# ESP8266_1wire_Gateway.net
KiCad netlist of a schematic drawn in EAGLE
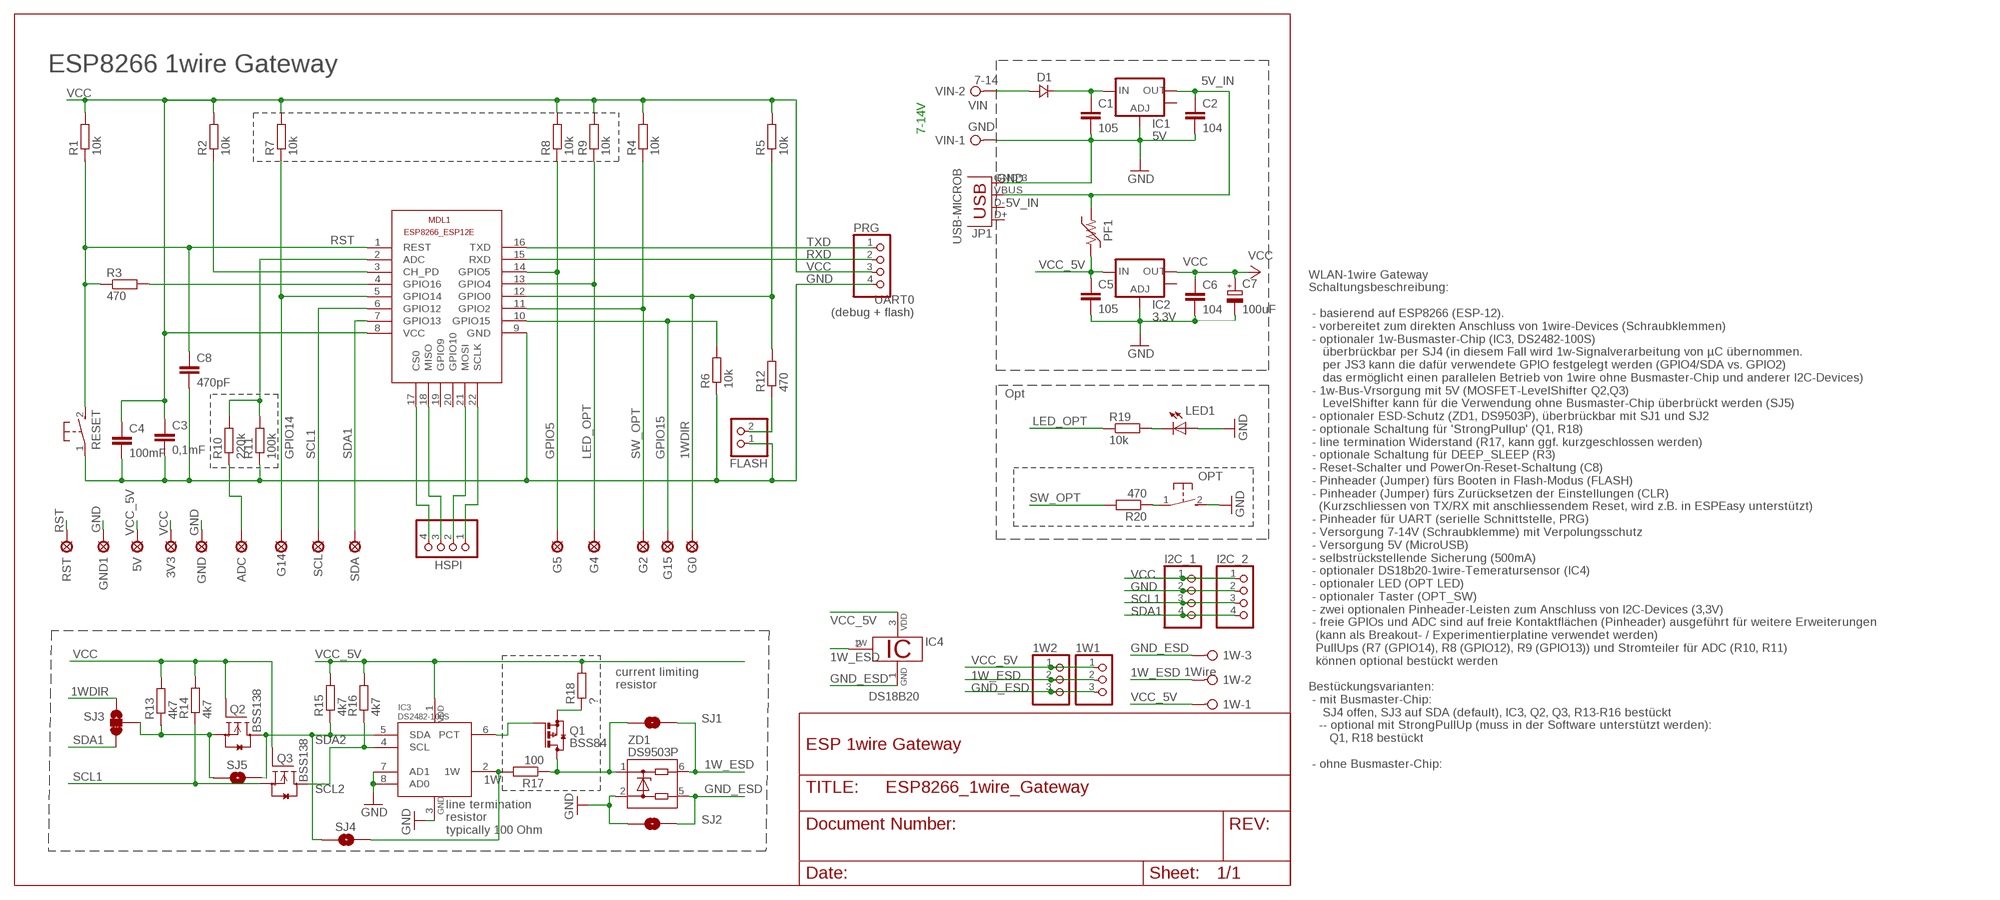
[diagram p0: schematic, sheet 1]

(export (version "E")
  (design (tool "Eeschema 10.0.6"))
  (components
    (comp (ref "1W")
      (value "1Wire")
      (footprint "eagle-import:W237-133")
      (libsource (lib "eagle-import") (part "W237-03P"))
    )
    (comp (ref "1W1")
      (value "PINHD-1X3_S")
      (footprint "eagle-import:1X03")
      (libsource (lib "eagle-import") (part "PINHD-1X3_S"))
    )
    (comp (ref "1W2")
      (value "PINHD-1X3_S")
      (footprint "eagle-import:1X03")
      (libsource (lib "eagle-import") (part "PINHD-1X3_S"))
    )
    (comp (ref "3V3")
      (value "LSP10")
      (footprint "eagle-import:LSP10")
      (libsource (lib "eagle-import") (part "LSP10"))
    )
    (comp (ref "5V")
      (value "LSP10")
      (footprint "eagle-import:LSP10")
      (libsource (lib "eagle-import") (part "LSP10"))
    )
    (comp (ref "ADC")
      (value "LSP10")
      (footprint "eagle-import:LSP10")
      (libsource (lib "eagle-import") (part "LSP10"))
    )
    (comp (ref "C1")
      (value "105")
      (footprint "eagle-import:C0805")
      (libsource (lib "eagle-import") (part "C-EUC0805"))
    )
    (comp (ref "C2")
      (value "104")
      (footprint "eagle-import:C0805")
      (libsource (lib "eagle-import") (part "C-EUC0805"))
    )
    (comp (ref "C3")
      (value "0,1mF")
      (footprint "eagle-import:C0805")
      (libsource (lib "eagle-import") (part "C-EUC0805"))
    )
    (comp (ref "C4")
      (value "100mF")
      (footprint "eagle-import:C1210")
      (libsource (lib "eagle-import") (part "C-EUC1210"))
    )
    (comp (ref "C5")
      (value "105")
      (footprint "eagle-import:C0805")
      (libsource (lib "eagle-import") (part "C-EUC0805"))
    )
    (comp (ref "C6")
      (value "104")
      (footprint "eagle-import:C0805")
      (libsource (lib "eagle-import") (part "C-EUC0805"))
    )
    (comp (ref "C7")
      (value "100uF")
      (footprint "eagle-import:E2,5-6E")
      (libsource (lib "eagle-import") (part "CPOL-EUE2,5-6E"))
    )
    (comp (ref "C8")
      (value "470pF")
      (footprint "eagle-import:C0805")
      (libsource (lib "eagle-import") (part "C-EUC0805"))
    )
    (comp (ref "D1")
      (value "SS14")
      (footprint "eagle-import:DO214")
      (libsource (lib "eagle-import") (part "SS14"))
    )
    (comp (ref "FLASH")
      (value "PINHD-1X2_S")
      (footprint "eagle-import:1X02")
      (libsource (lib "eagle-import") (part "PINHD-1X2_S"))
    )
    (comp (ref "G0")
      (value "LSP10")
      (footprint "eagle-import:LSP10")
      (libsource (lib "eagle-import") (part "LSP10"))
    )
    (comp (ref "G2")
      (value "LSP10")
      (footprint "eagle-import:LSP10")
      (libsource (lib "eagle-import") (part "LSP10"))
    )
    (comp (ref "G4")
      (value "LSP10")
      (footprint "eagle-import:LSP10")
      (libsource (lib "eagle-import") (part "LSP10"))
    )
    (comp (ref "G5")
      (value "LSP10")
      (footprint "eagle-import:LSP10")
      (libsource (lib "eagle-import") (part "LSP10"))
    )
    (comp (ref "G14")
      (value "LSP10")
      (footprint "eagle-import:LSP10")
      (libsource (lib "eagle-import") (part "LSP10"))
    )
    (comp (ref "G15")
      (value "LSP10")
      (footprint "eagle-import:LSP10")
      (libsource (lib "eagle-import") (part "LSP10"))
    )
    (comp (ref "GND")
      (value "LSP10")
      (footprint "eagle-import:LSP10")
      (libsource (lib "eagle-import") (part "LSP10"))
    )
    (comp (ref "GND1")
      (value "GND")
      (footprint "eagle-import:LSP10")
      (libsource (lib "eagle-import") (part "LSP10"))
    )
    (comp (ref "HSPI")
      (value "PINHD-1X4_S")
      (footprint "eagle-import:1X04")
      (libsource (lib "eagle-import") (part "PINHD-1X4_S"))
    )
    (comp (ref "I2C_1")
      (value "PINHD-1X4_S")
      (footprint "eagle-import:1X04")
      (libsource (lib "eagle-import") (part "PINHD-1X4_S"))
    )
    (comp (ref "I2C_2")
      (value "PINHD-1X4_S")
      (footprint "eagle-import:1X04")
      (libsource (lib "eagle-import") (part "PINHD-1X4_S"))
    )
    (comp (ref "IC1")
      (value "5V")
      (footprint "eagle-import:SOT223")
      (libsource (lib "eagle-import") (part "V_REG_LM1117SOT223"))
    )
    (comp (ref "IC2")
      (value "3.3V")
      (footprint "eagle-import:SOT223")
      (libsource (lib "eagle-import") (part "V_REG_LM1117SOT223"))
    )
    (comp (ref "IC3")
      (value "DS2482-100S")
      (footprint "eagle-import:SO08")
      (libsource (lib "eagle-import") (part "DS2482-100S"))
    )
    (comp (ref "IC4")
      (value "DS18B20")
      (footprint "eagle-import:TO92-")
      (libsource (lib "eagle-import") (part "DS18B20"))
    )
    (comp (ref "JP1")
      (value "USB-MICROB")
      (footprint "eagle-import:USB-MICROB")
      (libsource (lib "eagle-import") (part "USB-MICROB"))
    )
    (comp (ref "LED1")
      (value "CFG")
      (footprint "eagle-import:CHIPLED_1206")
      (libsource (lib "eagle-import") (part "LEDCHIPLED_1206"))
    )
    (comp (ref "MDL1")
      (value "µC")
      (footprint "eagle-import:ESP8266-ESP12E")
      (libsource (lib "eagle-import") (part "ESP8266-12EESP8266-ESP12E"))
    )
    (comp (ref "OPT")
      (value "DTSM-3")
      (footprint "eagle-import:DTSM-3")
      (libsource (lib "eagle-import") (part "DTSM-3"))
    )
    (comp (ref "PF1")
      (value "500mA")
      (footprint "eagle-import:F1206")
      (libsource (lib "eagle-import") (part "PTC-F1206"))
    )
    (comp (ref "PRG")
      (value "PINHD-1X4_S")
      (footprint "eagle-import:1X04")
      (libsource (lib "eagle-import") (part "PINHD-1X4_S"))
    )
    (comp (ref "Q1")
      (value "BSS84")
      (footprint "eagle-import:SOT23")
      (libsource (lib "eagle-import") (part "BSS84"))
    )
    (comp (ref "Q2")
      (value "BSS138")
      (footprint "eagle-import:SOT23")
      (libsource (lib "eagle-import") (part "BSS138"))
    )
    (comp (ref "Q3")
      (value "BSS138")
      (footprint "eagle-import:SOT23")
      (libsource (lib "eagle-import") (part "BSS138"))
    )
    (comp (ref "R1")
      (value "10k")
      (footprint "eagle-import:R0805")
      (libsource (lib "eagle-import") (part "resistor_R-EU_R0805"))
    )
    (comp (ref "R2")
      (value "10k")
      (footprint "eagle-import:R0805")
      (libsource (lib "eagle-import") (part "resistor_R-EU_R0805"))
    )
    (comp (ref "R3")
      (value "470")
      (footprint "eagle-import:R0805")
      (libsource (lib "eagle-import") (part "resistor_R-EU_R0805"))
    )
    (comp (ref "R4")
      (value "10k")
      (footprint "eagle-import:R0805")
      (libsource (lib "eagle-import") (part "resistor_R-EU_R0805"))
    )
    (comp (ref "R5")
      (value "10k")
      (footprint "eagle-import:R0805")
      (libsource (lib "eagle-import") (part "resistor_R-EU_R0805"))
    )
    (comp (ref "R6")
      (value "10k")
      (footprint "eagle-import:R0805")
      (libsource (lib "eagle-import") (part "resistor_R-EU_R0805"))
    )
    (comp (ref "R7")
      (value "10k")
      (footprint "eagle-import:R0805")
      (libsource (lib "eagle-import") (part "resistor_R-EU_R0805"))
    )
    (comp (ref "R8")
      (value "10k")
      (footprint "eagle-import:R0805")
      (libsource (lib "eagle-import") (part "resistor_R-EU_R0805"))
    )
    (comp (ref "R9")
      (value "10k")
      (footprint "eagle-import:R0805")
      (libsource (lib "eagle-import") (part "resistor_R-EU_R0805"))
    )
    (comp (ref "R10")
      (value "220k")
      (footprint "eagle-import:R0805")
      (libsource (lib "eagle-import") (part "resistor_R-EU_R0805"))
    )
    (comp (ref "R11")
      (value "100k")
      (footprint "eagle-import:R0805")
      (libsource (lib "eagle-import") (part "resistor_R-EU_R0805"))
    )
    (comp (ref "R12")
      (value "470")
      (footprint "eagle-import:R0805")
      (libsource (lib "eagle-import") (part "resistor_R-EU_R0805"))
    )
    (comp (ref "R13")
      (value "4k7")
      (footprint "eagle-import:R0805")
      (libsource (lib "eagle-import") (part "resistor_R-EU_R0805"))
    )
    (comp (ref "R14")
      (value "4k7")
      (footprint "eagle-import:R0805")
      (libsource (lib "eagle-import") (part "resistor_R-EU_R0805"))
    )
    (comp (ref "R15")
      (value "4k7")
      (footprint "eagle-import:R0805")
      (libsource (lib "eagle-import") (part "resistor_R-EU_R0805"))
    )
    (comp (ref "R16")
      (value "4k7")
      (footprint "eagle-import:R0805")
      (libsource (lib "eagle-import") (part "resistor_R-EU_R0805"))
    )
    (comp (ref "R17")
      (value "100")
      (footprint "eagle-import:R0805_SMALL_GAP")
      (libsource (lib "eagle-import") (part "R0805_SMALL_GAP"))
    )
    (comp (ref "R18")
      (value "?")
      (footprint "eagle-import:R0805_SMALL_GAP")
      (libsource (lib "eagle-import") (part "R0805_SMALL_GAP"))
    )
    (comp (ref "R19")
      (value "10k")
      (footprint "eagle-import:R0805")
      (libsource (lib "eagle-import") (part "R-EU_R0805"))
    )
    (comp (ref "R20")
      (value "470")
      (footprint "eagle-import:R0805")
      (libsource (lib "eagle-import") (part "resistor_R-EU_R0805"))
    )
    (comp (ref "RESET")
      (value "DTSM-3")
      (footprint "eagle-import:DTSM-3")
      (libsource (lib "eagle-import") (part "DTSM-3"))
    )
    (comp (ref "RST")
      (value "RST")
      (footprint "eagle-import:LSP10")
      (libsource (lib "eagle-import") (part "LSP10"))
    )
    (comp (ref "SCL")
      (value "LSP10")
      (footprint "eagle-import:LSP10")
      (libsource (lib "eagle-import") (part "LSP10"))
    )
    (comp (ref "SDA")
      (value "LSP10")
      (footprint "eagle-import:LSP10")
      (libsource (lib "eagle-import") (part "LSP10"))
    )
    (comp (ref "SJ1")
      (value "JUMPER-PAD-2-NOYES_SILK")
      (footprint "eagle-import:PAD-JUMPER-2-NO_YES_SILK")
      (libsource (lib "eagle-import") (part "JUMPER-PAD-2-NOYES_SILK"))
    )
    (comp (ref "SJ2")
      (value "JUMPER-PAD-2-NOYES_SILK")
      (footprint "eagle-import:PAD-JUMPER-2-NO_YES_SILK")
      (libsource (lib "eagle-import") (part "JUMPER-PAD-2-NOYES_SILK"))
    )
    (comp (ref "SJ3")
      (value "JUMPER-PAD-3-2OF3_NC_BY_TRACE_SMALL")
      (footprint "eagle-import:PAD-JUMPER-3-2OF3_NC_BY_TRACE_YES_SILK_FULL_BOX")
      (libsource (lib "eagle-import") (part "JUMPER-PAD-3-2OF3_NC_BY_TRACE_SMALL"))
    )
    (comp (ref "SJ4")
      (value "JUMPER-PAD-2-NOYES_SILK")
      (footprint "eagle-import:PAD-JUMPER-2-NO_YES_SILK")
      (libsource (lib "eagle-import") (part "JUMPER-PAD-2-NOYES_SILK"))
    )
    (comp (ref "SJ5")
      (value "JUMPER-PAD-2-NOYES_SILK")
      (footprint "eagle-import:PAD-JUMPER-2-NO_YES_SILK")
      (libsource (lib "eagle-import") (part "JUMPER-PAD-2-NOYES_SILK"))
    )
    (comp (ref "VIN")
      (value "7-14")
      (footprint "eagle-import:W237-132")
      (libsource (lib "eagle-import") (part "W237-02P"))
    )
    (comp (ref "ZD1")
      (value "DS9503P")
      (footprint "eagle-import:TSOC6")
      (libsource (lib "eagle-import") (part "DS9503P"))
    )
  )
  (nets
    (net (code "1") (name "/1W") (class "Default")
      (node (ref "IC3") (pin "2") (pinfunction "1W_2") (pintype "open_collector"))
      (node (ref "R17") (pin "2") (pinfunction "2_2") (pintype "passive"))
      (node (ref "SJ4") (pin "1") (pinfunction "1_1") (pintype "passive"))
    )
    (net (code "2") (name "/1WDIR") (class "Default")
      (node (ref "G0") (pin "1") (pinfunction "MP_1") (pintype "passive"))
      (node (ref "MDL1") (pin "12") (pinfunction "GPIO0_12") (pintype "bidirectional"))
      (node (ref "R12") (pin "2") (pinfunction "2_2") (pintype "passive"))
      (node (ref "R5") (pin "1") (pinfunction "1_1") (pintype "passive"))
      (node (ref "SJ3") (pin "1") (pinfunction "1_1") (pintype "passive"))
    )
    (net (code "3") (name "/1W_ESD") (class "Default")
      (node (ref "1W") (pin "2") (pinfunction "KL_2") (pintype "passive"))
      (node (ref "1W1") (pin "2") (pinfunction "2_2") (pintype "passive"))
      (node (ref "1W2") (pin "2") (pinfunction "2_2") (pintype "passive"))
      (node (ref "IC4") (pin "2") (pinfunction "1W_2") (pintype "power_in"))
      (node (ref "SJ1") (pin "2") (pinfunction "2_2") (pintype "passive"))
      (node (ref "ZD1") (pin "6") (pinfunction "P$4_6") (pintype "passive"))
    )
    (net (code "4") (name "/5V_IN") (class "Default")
      (node (ref "C2") (pin "1") (pinfunction "1_1") (pintype "passive"))
      (node (ref "IC1") (pin "2") (pinfunction "OUT_2") (pintype "output"))
      (node (ref "JP1") (pin "VBUS") (pinfunction "VBUS_VBUS") (pintype "bidirectional"))
      (node (ref "PF1") (pin "2") (pinfunction "2_2") (pintype "passive"))
    )
    (net (code "5") (name "/GND_ESD") (class "Default")
      (node (ref "1W") (pin "3") (pinfunction "KL_3") (pintype "passive"))
      (node (ref "1W1") (pin "3") (pinfunction "3_3") (pintype "passive"))
      (node (ref "1W2") (pin "3") (pinfunction "3_3") (pintype "passive"))
      (node (ref "IC4") (pin "1") (pinfunction "GND_1") (pintype "power_in"))
      (node (ref "SJ2") (pin "2") (pinfunction "2_2") (pintype "passive"))
      (node (ref "ZD1") (pin "5") (pinfunction "P$3_5") (pintype "passive"))
    )
    (net (code "6") (name "/GPIO5") (class "Default")
      (node (ref "G5") (pin "1") (pinfunction "MP_1") (pintype "passive"))
      (node (ref "MDL1") (pin "14") (pinfunction "GPIO5_14") (pintype "bidirectional"))
      (node (ref "R8") (pin "1") (pinfunction "1_1") (pintype "passive"))
    )
    (net (code "7") (name "/GPIO14") (class "Default")
      (node (ref "G14") (pin "1") (pinfunction "MP_1") (pintype "passive"))
      (node (ref "MDL1") (pin "5") (pinfunction "GPIO14_5") (pintype "bidirectional"))
      (node (ref "R7") (pin "1") (pinfunction "1_1") (pintype "passive"))
    )
    (net (code "8") (name "/GPIO15") (class "Default")
      (node (ref "G15") (pin "1") (pinfunction "MP_1") (pintype "passive"))
      (node (ref "MDL1") (pin "10") (pinfunction "GPIO15_10") (pintype "bidirectional"))
      (node (ref "R6") (pin "2") (pinfunction "2_2") (pintype "passive"))
    )
    (net (code "9") (name "/LED_OPT") (class "Default")
      (node (ref "G4") (pin "1") (pinfunction "MP_1") (pintype "passive"))
      (node (ref "MDL1") (pin "13") (pinfunction "GPIO4_13") (pintype "bidirectional"))
      (node (ref "R19") (pin "1") (pinfunction "1_1") (pintype "passive"))
      (node (ref "R9") (pin "1") (pinfunction "1_1") (pintype "passive"))
    )
    (net (code "10") (name "/RST") (class "Default")
      (node (ref "C8") (pin "1") (pinfunction "1_1") (pintype "passive"))
      (node (ref "MDL1") (pin "1") (pinfunction "REST_1") (pintype "bidirectional"))
      (node (ref "R1") (pin "1") (pinfunction "1_1") (pintype "passive"))
      (node (ref "R3") (pin "1") (pinfunction "1_1") (pintype "passive"))
      (node (ref "RESET") (pin "2") (pinfunction "2_2") (pintype "passive"))
      (node (ref "RST") (pin "1") (pinfunction "MP_1") (pintype "passive"))
    )
    (net (code "11") (name "/RXD") (class "Default")
      (node (ref "MDL1") (pin "15") (pinfunction "RXD_15") (pintype "bidirectional"))
      (node (ref "PRG") (pin "2") (pinfunction "2_2") (pintype "passive"))
    )
    (net (code "12") (name "/SCL1") (class "Default")
      (node (ref "I2C_1") (pin "3") (pinfunction "3_3") (pintype "passive"))
      (node (ref "I2C_2") (pin "3") (pinfunction "3_3") (pintype "passive"))
      (node (ref "MDL1") (pin "6") (pinfunction "GPIO12_6") (pintype "bidirectional"))
      (node (ref "Q3") (pin "2") (pinfunction "S_2") (pintype "passive"))
      (node (ref "R14") (pin "1") (pinfunction "1_1") (pintype "passive"))
      (node (ref "SCL") (pin "1") (pinfunction "MP_1") (pintype "passive"))
    )
    (net (code "13") (name "/SCL2") (class "Default")
      (node (ref "IC3") (pin "4") (pinfunction "SCL_4") (pintype "input"))
      (node (ref "Q3") (pin "3") (pinfunction "D_3") (pintype "passive"))
      (node (ref "R16") (pin "1") (pinfunction "1_1") (pintype "passive"))
    )
    (net (code "14") (name "/SDA1") (class "Default")
      (node (ref "I2C_1") (pin "4") (pinfunction "4_4") (pintype "passive"))
      (node (ref "I2C_2") (pin "4") (pinfunction "4_4") (pintype "passive"))
      (node (ref "MDL1") (pin "7") (pinfunction "GPIO13_7") (pintype "bidirectional"))
      (node (ref "SDA") (pin "1") (pinfunction "MP_1") (pintype "passive"))
      (node (ref "SJ3") (pin "3") (pinfunction "3_3") (pintype "passive"))
    )
    (net (code "15") (name "/SDA2") (class "Default")
      (node (ref "IC3") (pin "5") (pinfunction "SDA_5") (pintype "bidirectional"))
      (node (ref "Q2") (pin "3") (pinfunction "D_3") (pintype "passive"))
      (node (ref "R15") (pin "1") (pinfunction "1_1") (pintype "passive"))
      (node (ref "SJ4") (pin "2") (pinfunction "2_2") (pintype "passive"))
      (node (ref "SJ5") (pin "1") (pinfunction "1_1") (pintype "passive"))
    )
    (net (code "16") (name "/SW_OPT") (class "Default")
      (node (ref "G2") (pin "1") (pinfunction "MP_1") (pintype "passive"))
      (node (ref "MDL1") (pin "11") (pinfunction "GPIO2_11") (pintype "bidirectional"))
      (node (ref "R20") (pin "2") (pinfunction "2_2") (pintype "passive"))
      (node (ref "R4") (pin "1") (pinfunction "1_1") (pintype "passive"))
    )
    (net (code "17") (name "/TXD") (class "Default")
      (node (ref "MDL1") (pin "16") (pinfunction "TXD_16") (pintype "bidirectional"))
      (node (ref "PRG") (pin "1") (pinfunction "1_1") (pintype "passive"))
    )
    (net (code "18") (name "/VCC_5V") (class "Default")
      (node (ref "1W") (pin "1") (pinfunction "KL_1") (pintype "passive"))
      (node (ref "1W1") (pin "1") (pinfunction "1_1") (pintype "passive"))
      (node (ref "1W2") (pin "1") (pinfunction "1_1") (pintype "passive"))
      (node (ref "5V") (pin "1") (pinfunction "MP_1") (pintype "passive"))
      (node (ref "C5") (pin "1") (pinfunction "1_1") (pintype "passive"))
      (node (ref "IC2") (pin "3") (pinfunction "IN_3") (pintype "input"))
      (node (ref "IC3") (pin "1") (pinfunction "VDD_1") (pintype "power_in"))
      (node (ref "IC4") (pin "3") (pinfunction "VDD_3") (pintype "power_in"))
      (node (ref "PF1") (pin "1") (pinfunction "1_1") (pintype "passive"))
      (node (ref "R15") (pin "2") (pinfunction "2_2") (pintype "passive"))
      (node (ref "R16") (pin "2") (pinfunction "2_2") (pintype "passive"))
      (node (ref "R18") (pin "2") (pinfunction "2_2") (pintype "passive"))
    )
    (net (code "19") (name "/VIN") (class "Default")
      (node (ref "D1") (pin "ANODE") (pinfunction "ANODE_ANODE") (pintype "bidirectional"))
      (node (ref "VIN") (pin "2") (pinfunction "KL_2") (pintype "passive"))
    )
    (net (code "20") (name "GND") (class "Default")
      (node (ref "C1") (pin "2") (pinfunction "2_2") (pintype "passive"))
      (node (ref "C2") (pin "2") (pinfunction "2_2") (pintype "passive"))
      (node (ref "C3") (pin "2") (pinfunction "2_2") (pintype "passive"))
      (node (ref "C4") (pin "2") (pinfunction "2_2") (pintype "passive"))
      (node (ref "C5") (pin "2") (pinfunction "2_2") (pintype "passive"))
      (node (ref "C6") (pin "2") (pinfunction "2_2") (pintype "passive"))
      (node (ref "C7") (pin "-") (pinfunction "-_-") (pintype "passive"))
      (node (ref "C8") (pin "2") (pinfunction "2_2") (pintype "passive"))
      (node (ref "FLASH") (pin "1") (pinfunction "1_1") (pintype "passive"))
      (node (ref "GND") (pin "1") (pinfunction "MP_1") (pintype "passive"))
      (node (ref "GND1") (pin "1") (pinfunction "MP_1") (pintype "passive"))
      (node (ref "I2C_1") (pin "2") (pinfunction "2_2") (pintype "passive"))
      (node (ref "I2C_2") (pin "2") (pinfunction "2_2") (pintype "passive"))
      (node (ref "IC1") (pin "1") (pinfunction "ADJ_1") (pintype "input"))
      (node (ref "IC2") (pin "1") (pinfunction "ADJ_1") (pintype "input"))
      (node (ref "IC3") (pin "3") (pinfunction "GND_3") (pintype "power_in"))
      (node (ref "IC3") (pin "7") (pinfunction "AD1_7") (pintype "input"))
      (node (ref "IC3") (pin "8") (pinfunction "AD0_8") (pintype "input"))
      (node (ref "JP1") (pin "GND") (pinfunction "GND_GND") (pintype "bidirectional"))
      (node (ref "JP1") (pin "MT1") (pinfunction "GND_MT1") (pintype "bidirectional"))
      (node (ref "JP1") (pin "MT2") (pinfunction "GND_MT2") (pintype "bidirectional"))
      (node (ref "LED1") (pin "A") (pinfunction "A_A") (pintype "passive"))
      (node (ref "MDL1") (pin "9") (pinfunction "GND_9") (pintype "bidirectional"))
      (node (ref "OPT") (pin "2") (pinfunction "2_2") (pintype "passive"))
      (node (ref "PRG") (pin "4") (pinfunction "4_4") (pintype "passive"))
      (node (ref "R11") (pin "1") (pinfunction "1_1") (pintype "passive"))
      (node (ref "R6") (pin "1") (pinfunction "1_1") (pintype "passive"))
      (node (ref "RESET") (pin "1") (pinfunction "1_1") (pintype "passive"))
      (node (ref "SJ2") (pin "1") (pinfunction "1_1") (pintype "passive"))
      (node (ref "VIN") (pin "1") (pinfunction "KL_1") (pintype "passive"))
      (node (ref "ZD1") (pin "2") (pinfunction "P$2_2") (pintype "passive"))
    )
    (net (code "21") (name "Net-(ADC-MP)") (class "Default")
      (node (ref "ADC") (pin "1") (pinfunction "MP_1") (pintype "passive"))
      (node (ref "R10") (pin "1") (pinfunction "1_1") (pintype "passive"))
    )
    (net (code "22") (name "Net-(FLASH-Pad2)") (class "Default")
      (node (ref "FLASH") (pin "2") (pinfunction "2_2") (pintype "passive"))
      (node (ref "R12") (pin "1") (pinfunction "1_1") (pintype "passive"))
    )
    (net (code "23") (name "Net-(IC1-IN)") (class "Default")
      (node (ref "C1") (pin "1") (pinfunction "1_1") (pintype "passive"))
      (node (ref "D1") (pin "CATHODE") (pinfunction "CATHODE_CATHODE") (pintype "bidirectional"))
      (node (ref "IC1") (pin "3") (pinfunction "IN_3") (pintype "input"))
    )
    (net (code "24") (name "Net-(IC3-PCT)") (class "Default")
      (node (ref "IC3") (pin "6") (pinfunction "PCT_6") (pintype "output"))
      (node (ref "Q1") (pin "1") (pinfunction "G_1") (pintype "passive"))
    )
    (net (code "25") (name "Net-(LED1-PadC)") (class "Default")
      (node (ref "LED1") (pin "C") (pinfunction "C_C") (pintype "passive"))
      (node (ref "R19") (pin "2") (pinfunction "2_2") (pintype "passive"))
    )
    (net (code "26") (name "Net-(MDL1-ADC)") (class "Default")
      (node (ref "MDL1") (pin "2") (pinfunction "ADC_2") (pintype "bidirectional"))
      (node (ref "R10") (pin "2") (pinfunction "2_2") (pintype "passive"))
      (node (ref "R11") (pin "2") (pinfunction "2_2") (pintype "passive"))
    )
    (net (code "27") (name "Net-(MDL1-CH_PD)") (class "Default")
      (node (ref "MDL1") (pin "3") (pinfunction "CH_PD_3") (pintype "bidirectional"))
      (node (ref "R2") (pin "1") (pinfunction "1_1") (pintype "passive"))
    )
    (net (code "28") (name "Net-(MDL1-CS0)") (class "Default")
      (node (ref "HSPI") (pin "4") (pinfunction "4_4") (pintype "passive"))
      (node (ref "MDL1") (pin "17") (pinfunction "CS0_17") (pintype "bidirectional"))
    )
    (net (code "29") (name "Net-(MDL1-GPIO16)") (class "Default")
      (node (ref "MDL1") (pin "4") (pinfunction "GPIO16_4") (pintype "bidirectional"))
      (node (ref "R3") (pin "2") (pinfunction "2_2") (pintype "passive"))
    )
    (net (code "30") (name "Net-(MDL1-MISO)") (class "Default")
      (node (ref "HSPI") (pin "3") (pinfunction "3_3") (pintype "passive"))
      (node (ref "MDL1") (pin "18") (pinfunction "MISO_18") (pintype "bidirectional"))
    )
    (net (code "31") (name "Net-(MDL1-MOSI)") (class "Default")
      (node (ref "HSPI") (pin "2") (pinfunction "2_2") (pintype "passive"))
      (node (ref "MDL1") (pin "21") (pinfunction "MOSI_21") (pintype "bidirectional"))
    )
    (net (code "32") (name "Net-(MDL1-SCLK)") (class "Default")
      (node (ref "HSPI") (pin "1") (pinfunction "1_1") (pintype "passive"))
      (node (ref "MDL1") (pin "22") (pinfunction "SCLK_22") (pintype "bidirectional"))
    )
    (net (code "33") (name "Net-(OPT-Pad1)") (class "Default")
      (node (ref "OPT") (pin "1") (pinfunction "1_1") (pintype "passive"))
      (node (ref "R20") (pin "1") (pinfunction "1_1") (pintype "passive"))
    )
    (net (code "34") (name "Net-(Q1-D)") (class "Default")
      (node (ref "Q1") (pin "3") (pinfunction "D_3") (pintype "passive"))
      (node (ref "R17") (pin "1") (pinfunction "1_1") (pintype "passive"))
      (node (ref "SJ1") (pin "1") (pinfunction "1_1") (pintype "passive"))
      (node (ref "ZD1") (pin "1") (pinfunction "P$1_1") (pintype "passive"))
    )
    (net (code "35") (name "Net-(Q1-S)") (class "Default")
      (node (ref "Q1") (pin "2") (pinfunction "S_2") (pintype "passive"))
      (node (ref "R18") (pin "1") (pinfunction "1_1") (pintype "passive"))
    )
    (net (code "36") (name "Net-(Q2-S)") (class "Default")
      (node (ref "Q2") (pin "2") (pinfunction "S_2") (pintype "passive"))
      (node (ref "R13") (pin "1") (pinfunction "1_1") (pintype "passive"))
      (node (ref "SJ3") (pin "2") (pinfunction "2_2") (pintype "passive"))
      (node (ref "SJ5") (pin "2") (pinfunction "2_2") (pintype "passive"))
    )
    (net (code "37") (name "VCC") (class "Default")
      (node (ref "3V3") (pin "1") (pinfunction "MP_1") (pintype "passive"))
      (node (ref "C3") (pin "1") (pinfunction "1_1") (pintype "passive"))
      (node (ref "C4") (pin "1") (pinfunction "1_1") (pintype "passive"))
      (node (ref "C6") (pin "1") (pinfunction "1_1") (pintype "passive"))
      (node (ref "C7") (pin "+") (pinfunction "+_+") (pintype "passive"))
      (node (ref "I2C_1") (pin "1") (pinfunction "1_1") (pintype "passive"))
      (node (ref "I2C_2") (pin "1") (pinfunction "1_1") (pintype "passive"))
      (node (ref "IC2") (pin "2") (pinfunction "OUT_2") (pintype "output"))
      (node (ref "MDL1") (pin "8") (pinfunction "VCC_8") (pintype "bidirectional"))
      (node (ref "PRG") (pin "3") (pinfunction "3_3") (pintype "passive"))
      (node (ref "Q2") (pin "1") (pinfunction "G_1") (pintype "passive"))
      (node (ref "Q3") (pin "1") (pinfunction "G_1") (pintype "passive"))
      (node (ref "R1") (pin "2") (pinfunction "2_2") (pintype "passive"))
      (node (ref "R13") (pin "2") (pinfunction "2_2") (pintype "passive"))
      (node (ref "R14") (pin "2") (pinfunction "2_2") (pintype "passive"))
      (node (ref "R2") (pin "2") (pinfunction "2_2") (pintype "passive"))
      (node (ref "R4") (pin "2") (pinfunction "2_2") (pintype "passive"))
      (node (ref "R5") (pin "2") (pinfunction "2_2") (pintype "passive"))
      (node (ref "R7") (pin "2") (pinfunction "2_2") (pintype "passive"))
      (node (ref "R8") (pin "2") (pinfunction "2_2") (pintype "passive"))
      (node (ref "R9") (pin "2") (pinfunction "2_2") (pintype "passive"))
    )
    (net (code "38") (name "unconnected-(IC1-OUT-Pad4)") (class "Default")
      (node (ref "IC1") (pin "4") (pinfunction "OUT_4") (pintype "output"))
    )
    (net (code "39") (name "unconnected-(IC2-OUT-Pad4)") (class "Default")
      (node (ref "IC2") (pin "4") (pinfunction "OUT_4") (pintype "output"))
    )
    (net (code "40") (name "unconnected-(JP1-PadD+)") (class "Default")
      (node (ref "JP1") (pin "D+") (pinfunction "D+_D+") (pintype "bidirectional"))
    )
    (net (code "41") (name "unconnected-(JP1-PadD-)") (class "Default")
      (node (ref "JP1") (pin "D-") (pinfunction "D-_D-") (pintype "bidirectional"))
    )
    (net (code "42") (name "unconnected-(MDL1-GPIO9-Pad19)") (class "Default")
      (node (ref "MDL1") (pin "19") (pinfunction "GPIO9_19") (pintype "bidirectional"))
    )
    (net (code "43") (name "unconnected-(MDL1-GPIO10-Pad20)") (class "Default")
      (node (ref "MDL1") (pin "20") (pinfunction "GPIO10_20") (pintype "bidirectional"))
    )
  )
)
